# UART_com_Bluetooth.net
KiCad netlist of a schematic drawn in EAGLE
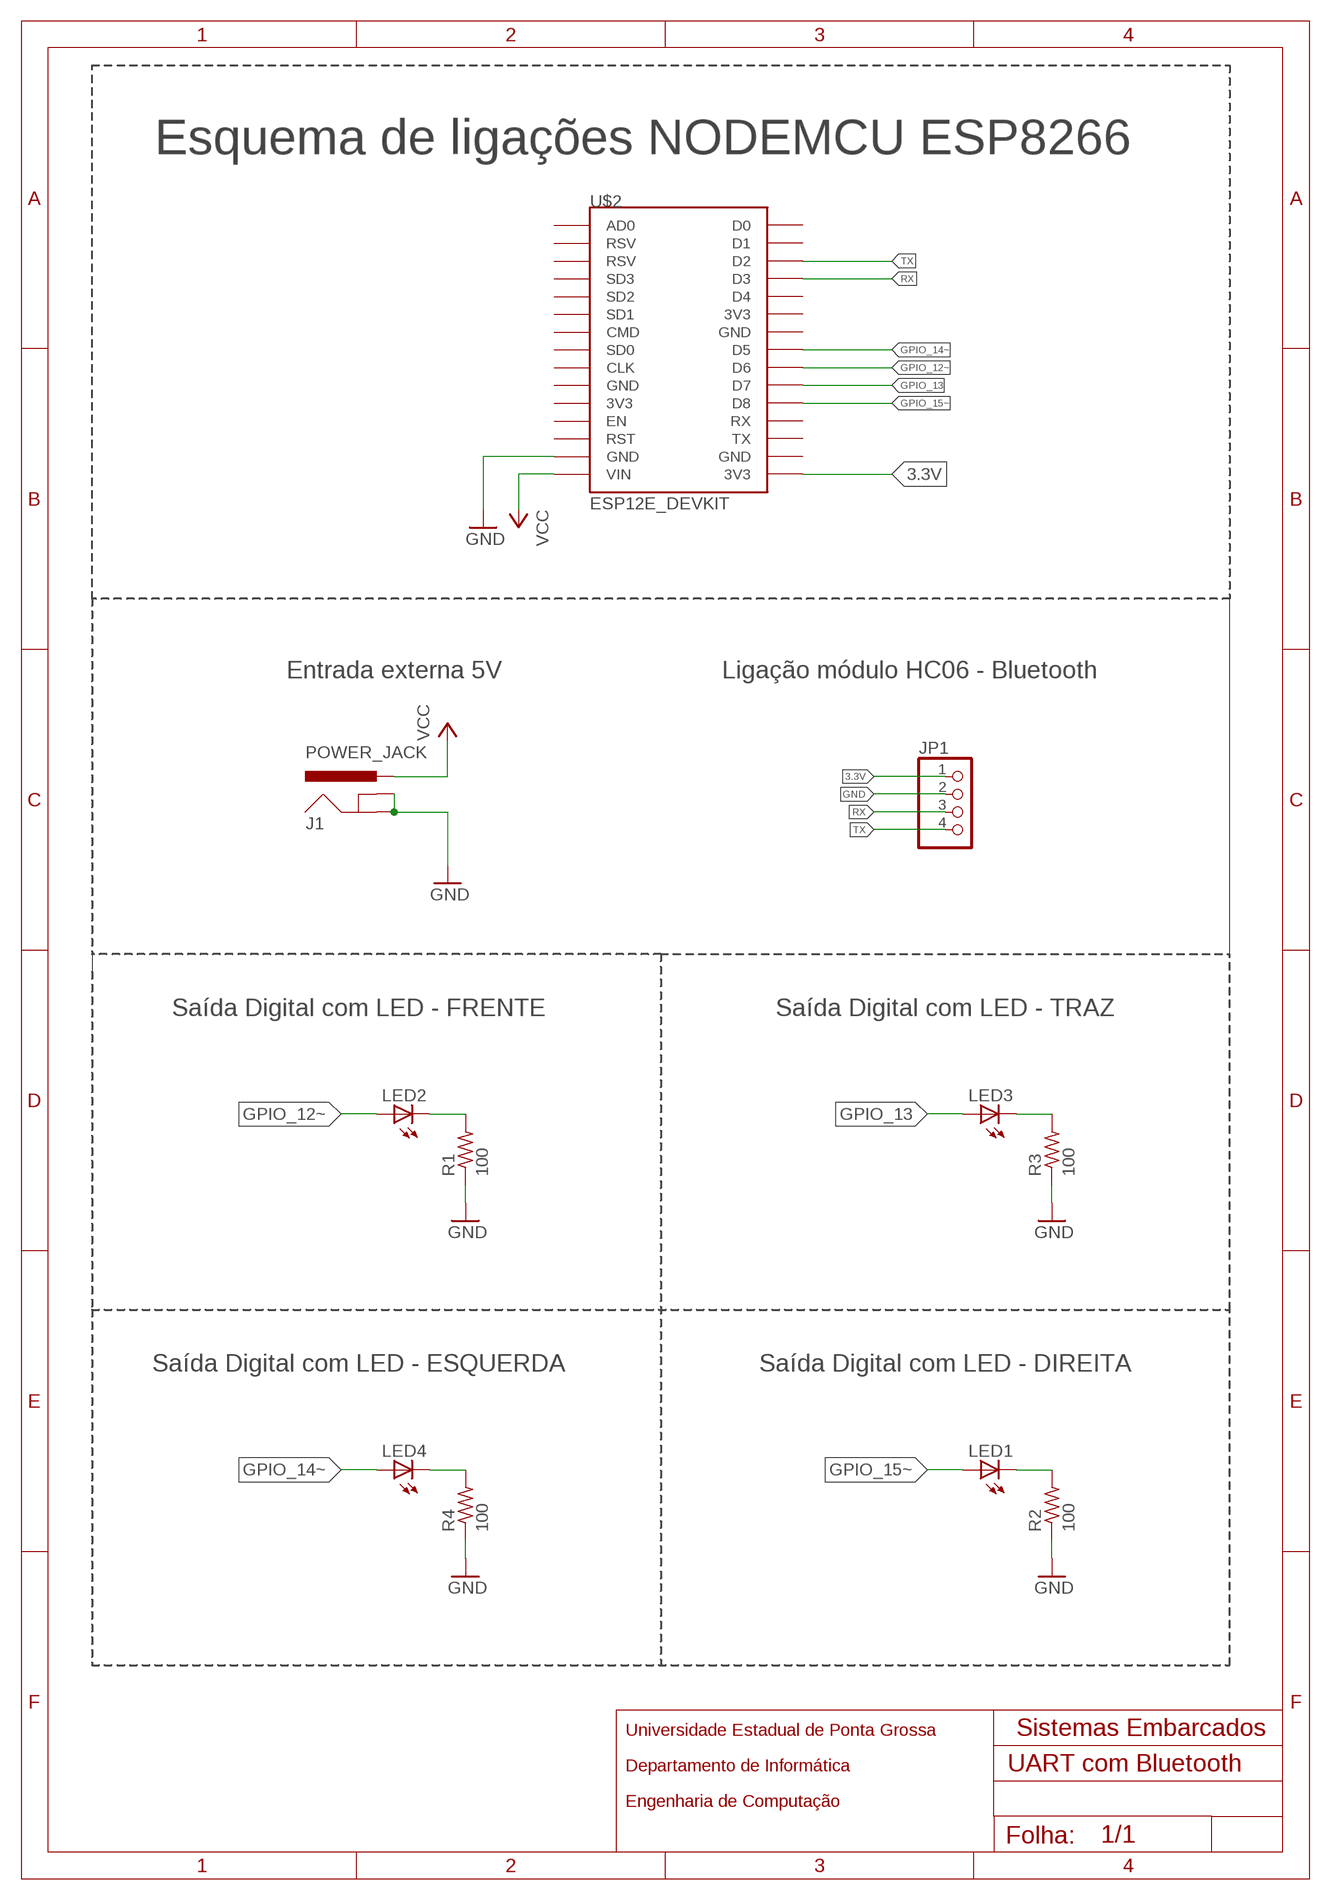
[diagram p0: schematic, sheet 1]

(export (version "E")
  (design (tool "Eeschema 10.0.6"))
  (components
    (comp (ref "J1")
      (value "POWER_JACK")
      (footprint "eagle-import:POWER_JACK_PTH")
      (libsource (lib "eagle-import") (part "POWER_JACK"))
    )
    (comp (ref "JP1")
      (value "PINHD-1X4")
      (footprint "eagle-import:1X04")
      (libsource (lib "eagle-import") (part "PINHD-1X4"))
    )
    (comp (ref "LED1")
      (value "LED5MM")
      (footprint "eagle-import:LED5MM")
      (libsource (lib "eagle-import") (part "LED5MM"))
    )
    (comp (ref "LED2")
      (value "LED5MM")
      (footprint "eagle-import:LED5MM")
      (libsource (lib "eagle-import") (part "LED5MM"))
    )
    (comp (ref "LED3")
      (value "LED5MM")
      (footprint "eagle-import:LED5MM")
      (libsource (lib "eagle-import") (part "LED5MM"))
    )
    (comp (ref "LED4")
      (value "LED5MM")
      (footprint "eagle-import:LED5MM")
      (libsource (lib "eagle-import") (part "LED5MM"))
    )
    (comp (ref "R1")
      (value "100")
      (footprint "eagle-import:0204_7")
      (libsource (lib "eagle-import") (part "R-US_0204/7"))
    )
    (comp (ref "R2")
      (value "100")
      (footprint "eagle-import:0204_7")
      (libsource (lib "eagle-import") (part "R-US_0204/7"))
    )
    (comp (ref "R3")
      (value "100")
      (footprint "eagle-import:0204_7")
      (libsource (lib "eagle-import") (part "R-US_0204/7"))
    )
    (comp (ref "R4")
      (value "100")
      (footprint "eagle-import:0204_7")
      (libsource (lib "eagle-import") (part "R-US_0204/7"))
    )
    (comp (ref "U$2")
      (value "ESP12E_DEVKIT")
      (footprint "eagle-import:ESP12E_DEVKIT")
      (libsource (lib "eagle-import") (part "ESP12E_DEVKIT"))
    )
  )
  (nets
    (net (code "1") (name "/GPIO_12~{}") (class "Default")
      (node (ref "LED2") (pin "A") (pinfunction "A_A") (pintype "passive"))
      (node (ref "U$2") (pin "D6") (pinfunction "D6_D6") (pintype "bidirectional"))
    )
    (net (code "2") (name "/GPIO_14~{}") (class "Default")
      (node (ref "LED4") (pin "A") (pinfunction "A_A") (pintype "passive"))
      (node (ref "U$2") (pin "D5") (pinfunction "D5_D5") (pintype "bidirectional"))
    )
    (net (code "3") (name "/GPIO_15~{}") (class "Default")
      (node (ref "LED1") (pin "A") (pinfunction "A_A") (pintype "passive"))
      (node (ref "U$2") (pin "D8") (pinfunction "D8_D8") (pintype "bidirectional"))
    )
    (net (code "4") (name "3.3V") (class "Default")
      (node (ref "JP1") (pin "1") (pinfunction "1_1") (pintype "passive"))
      (node (ref "U$2") (pin "3V3@2") (pinfunction "3V3_3V3@2") (pintype "bidirectional"))
    )
    (net (code "5") (name "GND") (class "Default")
      (node (ref "J1") (pin "GND") (pinfunction "GND_GND") (pintype "bidirectional"))
      (node (ref "J1") (pin "GNDBREAK") (pinfunction "GNDBREAK_GNDBREAK") (pintype "bidirectional"))
      (node (ref "JP1") (pin "2") (pinfunction "2_2") (pintype "passive"))
      (node (ref "R1") (pin "1") (pinfunction "1_1") (pintype "passive"))
      (node (ref "R2") (pin "1") (pinfunction "1_1") (pintype "passive"))
      (node (ref "R3") (pin "1") (pinfunction "1_1") (pintype "passive"))
      (node (ref "R4") (pin "1") (pinfunction "1_1") (pintype "passive"))
      (node (ref "U$2") (pin "GND@1") (pinfunction "GND_GND@1") (pintype "bidirectional"))
    )
    (net (code "6") (name "GPIO_13") (class "Default")
      (node (ref "LED3") (pin "A") (pinfunction "A_A") (pintype "passive"))
      (node (ref "U$2") (pin "D7") (pinfunction "D7_D7") (pintype "bidirectional"))
    )
    (net (code "7") (name "Net-(LED1-C)") (class "Default")
      (node (ref "LED1") (pin "K") (pinfunction "C_K") (pintype "passive"))
      (node (ref "R2") (pin "2") (pinfunction "2_2") (pintype "passive"))
    )
    (net (code "8") (name "Net-(LED2-C)") (class "Default")
      (node (ref "LED2") (pin "K") (pinfunction "C_K") (pintype "passive"))
      (node (ref "R1") (pin "2") (pinfunction "2_2") (pintype "passive"))
    )
    (net (code "9") (name "Net-(LED3-C)") (class "Default")
      (node (ref "LED3") (pin "K") (pinfunction "C_K") (pintype "passive"))
      (node (ref "R3") (pin "2") (pinfunction "2_2") (pintype "passive"))
    )
    (net (code "10") (name "Net-(LED4-C)") (class "Default")
      (node (ref "LED4") (pin "K") (pinfunction "C_K") (pintype "passive"))
      (node (ref "R4") (pin "2") (pinfunction "2_2") (pintype "passive"))
    )
    (net (code "11") (name "RX") (class "Default")
      (node (ref "JP1") (pin "3") (pinfunction "3_3") (pintype "passive"))
      (node (ref "U$2") (pin "D3") (pinfunction "D3_D3") (pintype "bidirectional"))
    )
    (net (code "12") (name "TX") (class "Default")
      (node (ref "JP1") (pin "4") (pinfunction "4_4") (pintype "passive"))
      (node (ref "U$2") (pin "D2") (pinfunction "D2_D2") (pintype "bidirectional"))
    )
    (net (code "13") (name "VCC") (class "Default")
      (node (ref "J1") (pin "PWR") (pinfunction "PWR_PWR") (pintype "bidirectional"))
      (node (ref "U$2") (pin "VIN") (pinfunction "VIN_VIN") (pintype "bidirectional"))
    )
    (net (code "14") (name "unconnected-(U$2-3V3-Pad3V3@0)") (class "Default")
      (node (ref "U$2") (pin "3V3@0") (pinfunction "3V3_3V3@0") (pintype "bidirectional"))
    )
    (net (code "15") (name "unconnected-(U$2-3V3-Pad3V3@1)") (class "Default")
      (node (ref "U$2") (pin "3V3@1") (pinfunction "3V3_3V3@1") (pintype "bidirectional"))
    )
    (net (code "16") (name "unconnected-(U$2-GND-PadGND@0)") (class "Default")
      (node (ref "U$2") (pin "GND@0") (pinfunction "GND_GND@0") (pintype "bidirectional"))
    )
    (net (code "17") (name "unconnected-(U$2-GND-PadGND@2)") (class "Default")
      (node (ref "U$2") (pin "GND@2") (pinfunction "GND_GND@2") (pintype "bidirectional"))
    )
    (net (code "18") (name "unconnected-(U$2-GND-PadGND@3)") (class "Default")
      (node (ref "U$2") (pin "GND@3") (pinfunction "GND_GND@3") (pintype "bidirectional"))
    )
    (net (code "19") (name "unconnected-(U$2-PadAD0)") (class "Default")
      (node (ref "U$2") (pin "AD0") (pinfunction "AD0_AD0") (pintype "bidirectional"))
    )
    (net (code "20") (name "unconnected-(U$2-PadCLK)") (class "Default")
      (node (ref "U$2") (pin "CLK") (pinfunction "CLK_CLK") (pintype "bidirectional"))
    )
    (net (code "21") (name "unconnected-(U$2-PadCMD)") (class "Default")
      (node (ref "U$2") (pin "CMD") (pinfunction "CMD_CMD") (pintype "bidirectional"))
    )
    (net (code "22") (name "unconnected-(U$2-PadD0)") (class "Default")
      (node (ref "U$2") (pin "D0") (pinfunction "D0_D0") (pintype "bidirectional"))
    )
    (net (code "23") (name "unconnected-(U$2-PadD1)") (class "Default")
      (node (ref "U$2") (pin "D1") (pinfunction "D1_D1") (pintype "bidirectional"))
    )
    (net (code "24") (name "unconnected-(U$2-PadD4)") (class "Default")
      (node (ref "U$2") (pin "D4") (pinfunction "D4_D4") (pintype "bidirectional"))
    )
    (net (code "25") (name "unconnected-(U$2-PadEN)") (class "Default")
      (node (ref "U$2") (pin "EN") (pinfunction "EN_EN") (pintype "bidirectional"))
    )
    (net (code "26") (name "unconnected-(U$2-PadRST)") (class "Default")
      (node (ref "U$2") (pin "RST") (pinfunction "RST_RST") (pintype "bidirectional"))
    )
    (net (code "27") (name "unconnected-(U$2-PadRX)") (class "Default")
      (node (ref "U$2") (pin "RX") (pinfunction "RX_RX") (pintype "bidirectional"))
    )
    (net (code "28") (name "unconnected-(U$2-PadSD0)") (class "Default")
      (node (ref "U$2") (pin "SD0") (pinfunction "SD0_SD0") (pintype "bidirectional"))
    )
    (net (code "29") (name "unconnected-(U$2-PadSD1)") (class "Default")
      (node (ref "U$2") (pin "SD1") (pinfunction "SD1_SD1") (pintype "bidirectional"))
    )
    (net (code "30") (name "unconnected-(U$2-PadSD2)") (class "Default")
      (node (ref "U$2") (pin "SD2") (pinfunction "SD2_SD2") (pintype "bidirectional"))
    )
    (net (code "31") (name "unconnected-(U$2-PadSD3)") (class "Default")
      (node (ref "U$2") (pin "SD3") (pinfunction "SD3_SD3") (pintype "bidirectional"))
    )
    (net (code "32") (name "unconnected-(U$2-PadTX)") (class "Default")
      (node (ref "U$2") (pin "TX") (pinfunction "TX_TX") (pintype "bidirectional"))
    )
    (net (code "33") (name "unconnected-(U$2-RSV-PadRSV@0)") (class "Default")
      (node (ref "U$2") (pin "RSV@0") (pinfunction "RSV_RSV@0") (pintype "bidirectional"))
    )
    (net (code "34") (name "unconnected-(U$2-RSV-PadRSV@1)") (class "Default")
      (node (ref "U$2") (pin "RSV@1") (pinfunction "RSV_RSV@1") (pintype "bidirectional"))
    )
  )
)
